# Sensor01.net
KiCad netlist of a schematic drawn in Altium Designer
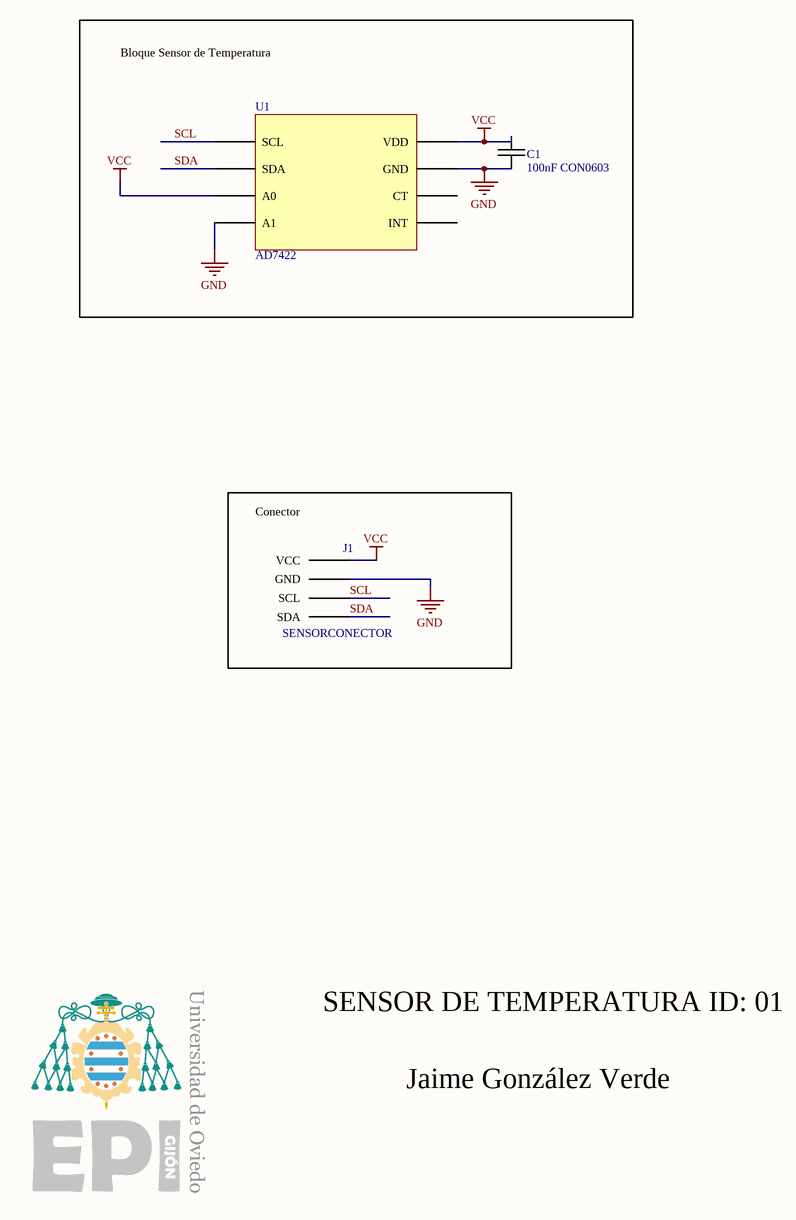
[diagram p0: Sensor01.SchDoc]

(export (version "E")
  (design (tool "Eeschema 10.0.6"))
  (components
    (comp (ref "C1")
      (value "100nF CON0603")
      (footprint "CAPC0603X06N")
      (libsource (lib "JaimeGlez") (part "CON0603"))
    )
    (comp (ref "J1")
      (value "SENSORCONECTOR")
      (footprint "ConectorSMD1,3mm")
      (libsource (lib "JaimeGlez") (part "SENSORCONECTOR"))
    )
    (comp (ref "U1") (value "AD7422") (footprint "ADT7422") (libsource (lib "JaimeGlez") (part "AD7422")))
  )
  (nets
    (net (code "1") (name "/SCL") (class "Default")
      (node (ref "J1") (pin "1") (pinfunction "SCL_1") (pintype "passive"))
      (node (ref "U1") (pin "1") (pinfunction "SCL_1") (pintype "passive"))
    )
    (net (code "2") (name "/SDA") (class "Default")
      (node (ref "J1") (pin "0") (pinfunction "SDA_0") (pintype "passive"))
      (node (ref "U1") (pin "2") (pinfunction "SDA_2") (pintype "passive"))
    )
    (net (code "3") (name "GND") (class "Default")
      (node (ref "C1") (pin "1") (pintype "passive"))
      (node (ref "J1") (pin "2") (pinfunction "GND_2") (pintype "passive"))
      (node (ref "U1") (pin "11") (pinfunction "GND_11") (pintype "passive"))
      (node (ref "U1") (pin "4") (pinfunction "A1_4") (pintype "passive"))
    )
    (net (code "4") (name "VCC") (class "Default")
      (node (ref "C1") (pin "2") (pintype "passive"))
      (node (ref "J1") (pin "3") (pinfunction "VCC_3") (pintype "passive"))
      (node (ref "U1") (pin "12") (pinfunction "VDD_12") (pintype "passive"))
      (node (ref "U1") (pin "3") (pinfunction "A0_3") (pintype "passive"))
    )
    (net (code "5") (name "unconnected-(U1-CT-Pad10)") (class "Default")
      (node (ref "U1") (pin "10") (pinfunction "CT_10") (pintype "passive"))
    )
    (net (code "6") (name "unconnected-(U1-INT-Pad9)") (class "Default")
      (node (ref "U1") (pin "9") (pinfunction "INT_9") (pintype "passive"))
    )
  )
)
